# STC32G12K128.net
KiCad netlist of a schematic drawn in Altium Designer
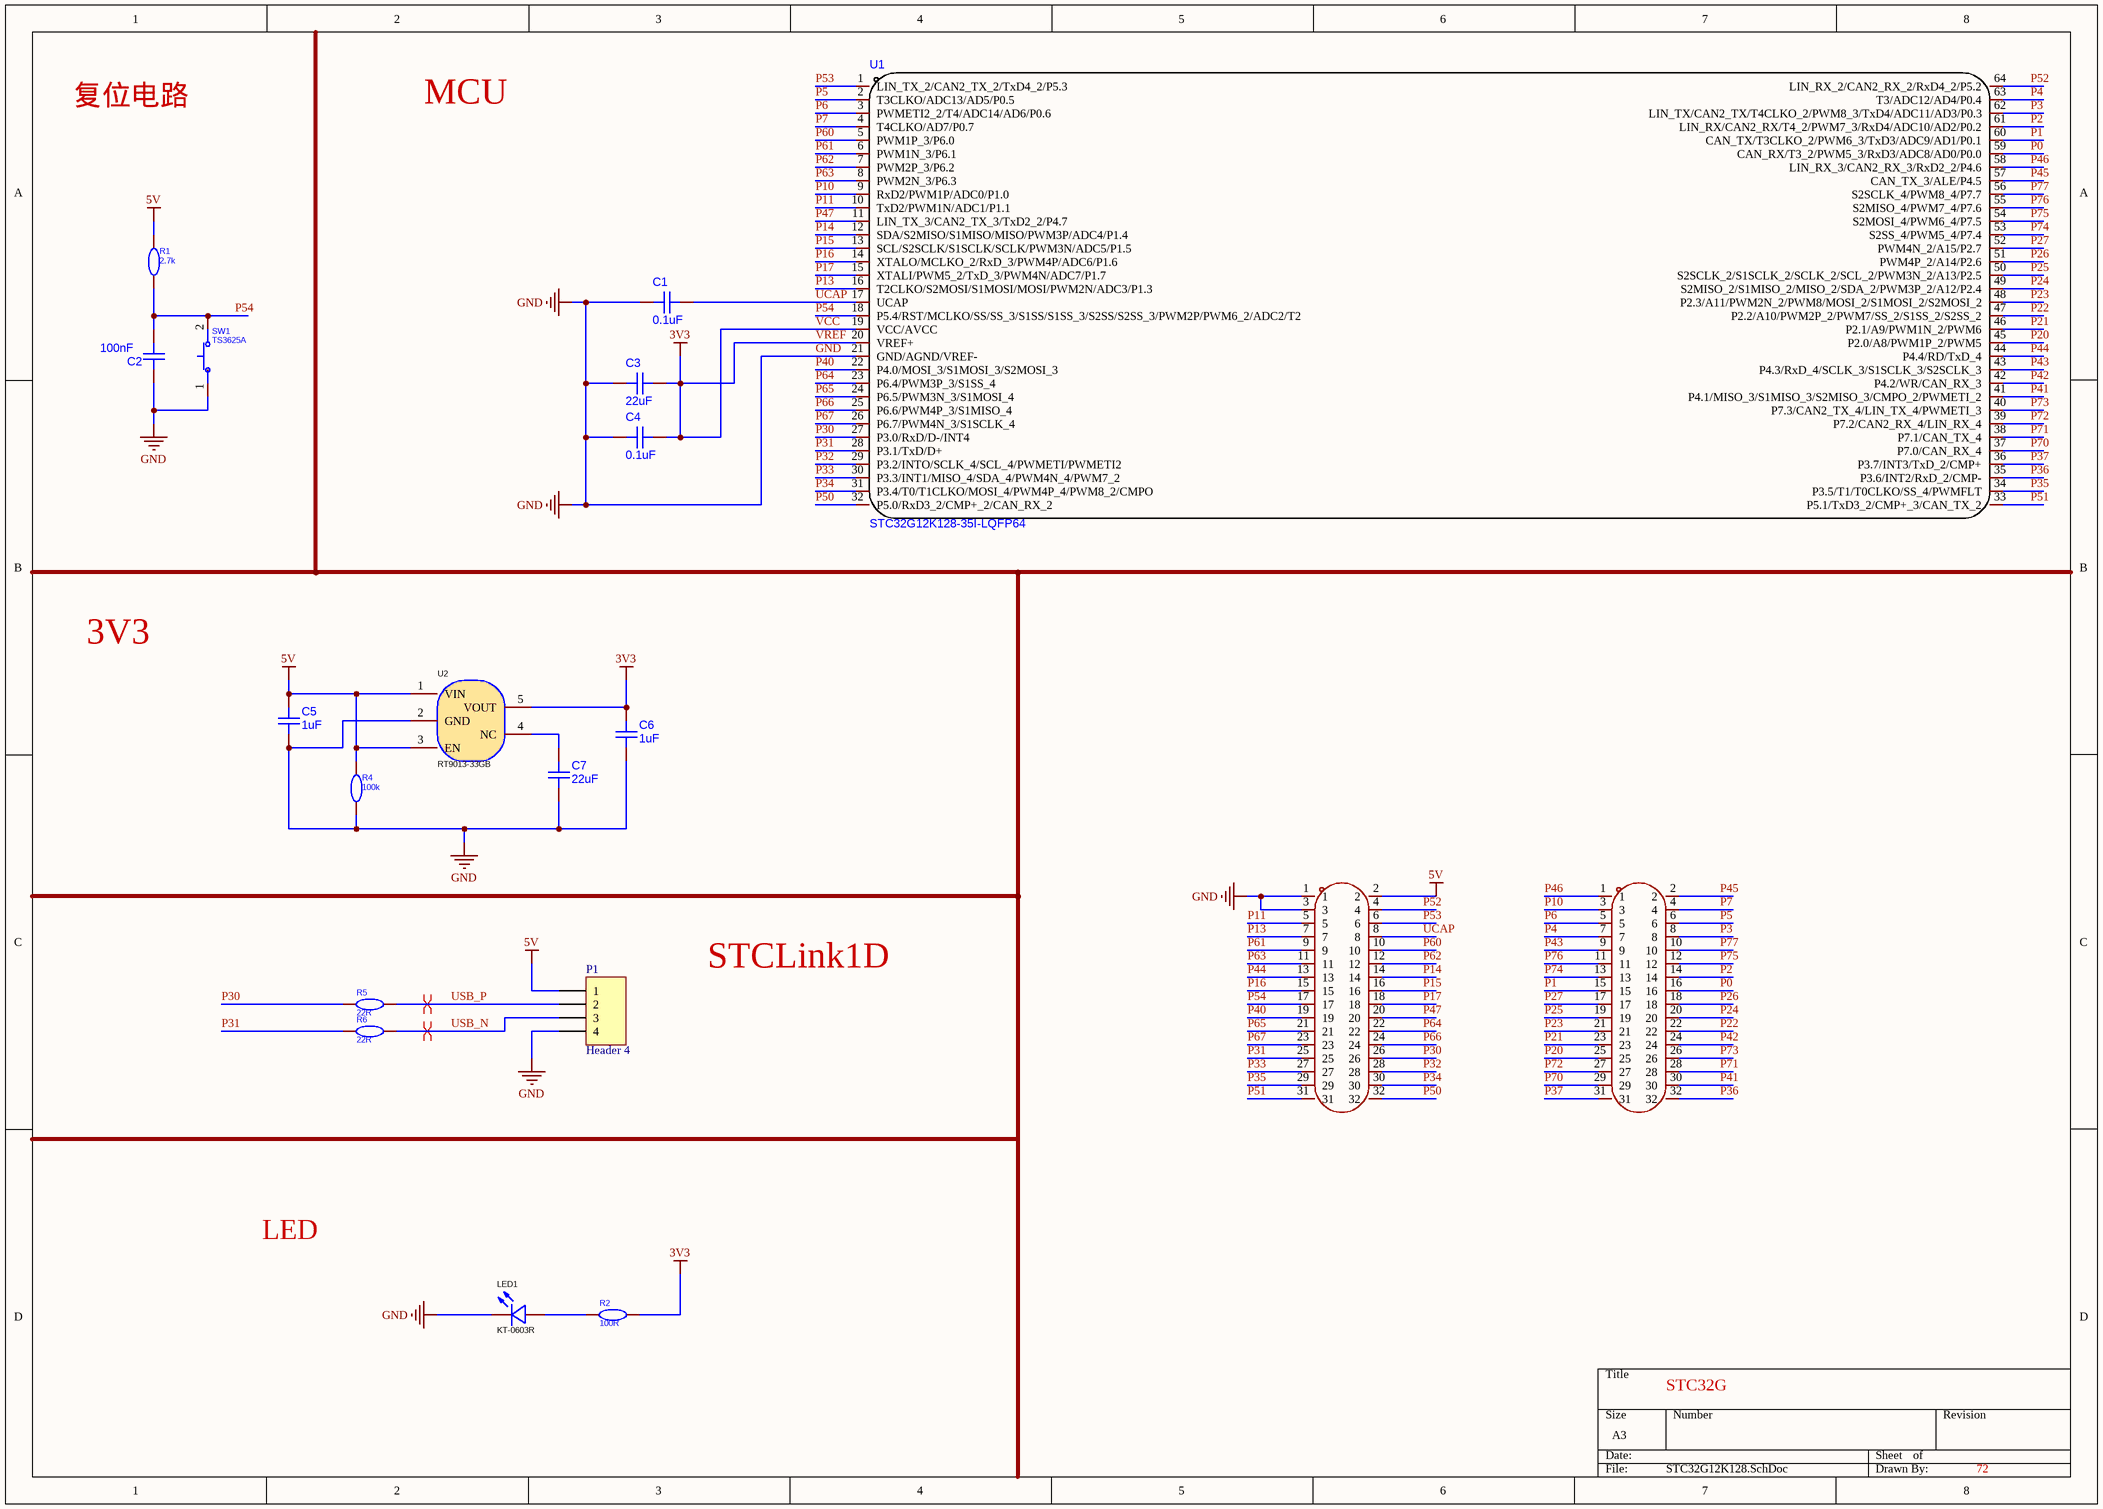
[diagram p0: STC32G12K128.SchDoc]

(export (version "E")
  (design (tool "Eeschema 10.0.6"))
  (components
    (comp (ref "C1")
      (value "0.1uF")
      (footprint "C0603:C0603")
      (fields
        (field (name "MANUFACTURER") "YAGEO(国巨)")
        (field (name "MANUFACTURER PART") "CC0603KRX7R9BB104")
        (field (name "TOLERANCE") "±10%")
      )
      (libsource (lib "CC0603KRX7R9BB1041_CC0603KRX7R9BB104") (part "CC0603KRX7R9BB104"))
    )
    (comp (ref "C2")
      (value "100nF")
      (footprint "C0603:C0603")
      (fields
        (field (name "MANUFACTURER") "YAGEO(国巨)")
        (field (name "MANUFACTURER PART") "CC0603KRX7R9BB104")
        (field (name "TOLERANCE") "±10%")
      )
      (libsource (lib "CC0603KRX7R9BB1041_CC0603KRX7R9BB104") (part "CC0603KRX7R9BB104"))
    )
    (comp (ref "C3")
      (value "22uF")
      (footprint "C0603:C0603")
      (fields
        (field (name "MANUFACTURER") "YAGEO(国巨)")
        (field (name "MANUFACTURER PART") "CC0603KRX7R9BB104")
        (field (name "TOLERANCE") "±10%")
      )
      (libsource (lib "CC0603KRX7R9BB1041_CC0603KRX7R9BB104") (part "CC0603KRX7R9BB104"))
    )
    (comp (ref "C4")
      (value "0.1uF")
      (footprint "C0603:C0603")
      (fields
        (field (name "MANUFACTURER") "YAGEO(国巨)")
        (field (name "MANUFACTURER PART") "CC0603KRX7R9BB104")
        (field (name "TOLERANCE") "±10%")
      )
      (libsource (lib "CC0603KRX7R9BB1041_CC0603KRX7R9BB104") (part "CC0603KRX7R9BB104"))
    )
    (comp (ref "C5")
      (value "1uF")
      (footprint "C0603:C0603")
      (fields
        (field (name "MANUFACTURER") "YAGEO(国巨)")
        (field (name "MANUFACTURER PART") "CC0603KRX7R9BB104")
        (field (name "TOLERANCE") "±10%")
      )
      (libsource (lib "CC0603KRX7R9BB1041_CC0603KRX7R9BB104") (part "CC0603KRX7R9BB104"))
    )
    (comp (ref "C6")
      (value "1uF")
      (footprint "C0603:C0603")
      (fields
        (field (name "MANUFACTURER") "YAGEO(国巨)")
        (field (name "MANUFACTURER PART") "CC0603KRX7R9BB104")
        (field (name "TOLERANCE") "±10%")
      )
      (libsource (lib "CC0603KRX7R9BB1041_CC0603KRX7R9BB104") (part "CC0603KRX7R9BB104"))
    )
    (comp (ref "C7")
      (value "22uF")
      (footprint "C0603:C0603")
      (fields
        (field (name "MANUFACTURER") "YAGEO(国巨)")
        (field (name "MANUFACTURER PART") "CC0603KRX7R9BB104")
        (field (name "TOLERANCE") "±10%")
      )
      (libsource (lib "CC0603KRX7R9BB1041_CC0603KRX7R9BB104") (part "CC0603KRX7R9BB104"))
    )
    (comp (ref "H1")
      (value "X6521WV-2x16H-C60D30")
      (footprint "HDR-TH_32P-2.54-V-M-R2-C16-S2.54:HDR-TH_32P-2.54-V-M-R2-C16-S2.54")
      (fields (field (name "MANUFACTURER") "XKB Connection(中国星坤)"))
      (libsource (lib "2×16H") (part "X6521WV-2x16H-C60D30"))
    )
    (comp (ref "H2")
      (value "X6521WV-2x16H-C60D30")
      (footprint "HDR-TH_32P-2.54-V-M-R2-C16-S2.54:HDR-TH_32P-2.54-V-M-R2-C16-S2.54")
      (fields (field (name "MANUFACTURER") "XKB Connection(中国星坤)"))
      (libsource (lib "2×16H") (part "X6521WV-2x16H-C60D30"))
    )
    (comp (ref "LED1")
      (value "KT-0603R")
      (footprint "LED0603-RD (1):LED0603-RD")
      (fields (field (name "MANUFACTURER") "KENTO"))
      (libsource (lib "LED-Red") (part "KT-0603R"))
    )
    (comp (ref "P1")
      (value "Header 4")
      (footprint "HDR1X4")
      (description "Header, 4-Pin")
      (fields (field (name "PUBLISHER") "Altium Limited"))
      (libsource (lib "Miscellaneous Connectors") (part "Header 4"))
    )
    (comp (ref "R1")
      (value "2.7k")
      (footprint "R0603:R0603")
      (fields
        (field (name "MANUFACTURER") "YAGEO(国巨)")
        (field (name "MANUFACTURER PART") "RC0603FR-074K7L")
        (field (name "TOLERANCE") "±1%")
      )
      (libsource (lib "4.7-0603") (part "RC0603FR-074K7L"))
    )
    (comp (ref "R2")
      (value "100R")
      (footprint "R0603:R0603")
      (fields
        (field (name "MANUFACTURER") "YAGEO(国巨)")
        (field (name "MANUFACTURER PART") "RC0603FR-074K7L")
        (field (name "TOLERANCE") "±1%")
      )
      (libsource (lib "4.7-0603") (part "RC0603FR-074K7L"))
    )
    (comp (ref "R4")
      (value "100k")
      (footprint "R0603:R0603")
      (fields
        (field (name "MANUFACTURER") "YAGEO(国巨)")
        (field (name "MANUFACTURER PART") "RC0603FR-074K7L")
        (field (name "TOLERANCE") "±1%")
      )
      (libsource (lib "4.7-0603") (part "RC0603FR-074K7L"))
    )
    (comp (ref "R5")
      (value "22R")
      (footprint "R0603:R0603")
      (fields
        (field (name "MANUFACTURER") "YAGEO(国巨)")
        (field (name "MANUFACTURER PART") "RC0603FR-074K7L")
        (field (name "TOLERANCE") "±1%")
      )
      (libsource (lib "4.7-0603") (part "RC0603FR-074K7L"))
    )
    (comp (ref "R6")
      (value "22R")
      (footprint "R0603:R0603")
      (fields
        (field (name "MANUFACTURER") "YAGEO(国巨)")
        (field (name "MANUFACTURER PART") "RC0603FR-074K7L")
        (field (name "TOLERANCE") "±1%")
      )
      (libsource (lib "4.7-0603") (part "RC0603FR-074K7L"))
    )
    (comp (ref "SW1")
      (value "TS3625A")
      (footprint "KEY-SMD_L6.0-W3.5-LS8.4:KEY-SMD_L6.0-W3.5-LS8.4")
      (fields (field (name "MANUFACTURER") "SHOU HAN(首韩)"))
      (libsource (lib "Button-SMD") (part "TS3625A"))
    )
    (comp (ref "U1")
      (value "STC32G12K128-35I-LQFP64")
      (footprint "LQFP-64_L10.0-W10.0-P0.50-LS12.0-BL:LQFP-64_L10.0-W10.0-P0.50-LS12.0-BL")
      (fields (field (name "MANUFACTURER") "STC(宏晶)"))
      (libsource (lib "STC32G12K128-35I-LQFP64") (part "STC32G12K128-35I-LQFP64"))
    )
    (comp (ref "U2")
      (value "RT9013-33GB")
      (footprint "SOT-23-5_L3.0-W1.7-P0.95-LS2.8-BL:SOT-23-5_L3.0-W1.7-P0.95-LS2.8-BL")
      (fields (field (name "MANUFACTURER") "RICHTEK(立锜)"))
      (libsource (lib "RT9013-33GB1_RT9013-33GB") (part "RT9013-33GB"))
    )
  )
  (nets
    (net (code "1") (name "/P0") (class "Default")
      (node (ref "H1") (pin "16") (pinfunction "16_16") (pintype "passive"))
      (node (ref "U1") (pin "59") (pinfunction "CAN_RX/T3_2/PWM5_3/RxD3/ADC8/AD0/P0.0_59") (pintype "passive"))
    )
    (net (code "2") (name "/P1") (class "Default")
      (node (ref "H1") (pin "15") (pinfunction "15_15") (pintype "passive"))
      (node (ref "U1") (pin "60") (pinfunction "CAN_TX/T3CLKO_2/PWM6_3/TxD3/ADC9/AD1/P0.1_60") (pintype "passive"))
    )
    (net (code "3") (name "/P2") (class "Default")
      (node (ref "H1") (pin "14") (pinfunction "14_14") (pintype "passive"))
      (node (ref "U1") (pin "61") (pinfunction "LIN_RX/CAN2_RX/T4_2/PWM7_3/RxD4/ADC10/AD2/P0.2_61") (pintype "passive"))
    )
    (net (code "4") (name "/P3") (class "Default")
      (node (ref "H1") (pin "8") (pinfunction "8_8") (pintype "passive"))
      (node (ref "U1") (pin "62") (pinfunction "LIN_TX/CAN2_TX/T4CLKO_2/PWM8_3/TxD4/ADC11/AD3/P0.3_62") (pintype "passive"))
    )
    (net (code "5") (name "/P4") (class "Default")
      (node (ref "H1") (pin "7") (pinfunction "7_7") (pintype "passive"))
      (node (ref "U1") (pin "63") (pinfunction "T3/ADC12/AD4/P0.4_63") (pintype "passive"))
    )
    (net (code "6") (name "/P5") (class "Default")
      (node (ref "H1") (pin "6") (pinfunction "6_6") (pintype "passive"))
      (node (ref "U1") (pin "2") (pinfunction "T3CLKO/ADC13/AD5/P0.5_2") (pintype "passive"))
    )
    (net (code "7") (name "/P6") (class "Default")
      (node (ref "H1") (pin "5") (pinfunction "5_5") (pintype "passive"))
      (node (ref "U1") (pin "3") (pinfunction "PWMETI2_2/T4/ADC14/AD6/P0.6_3") (pintype "passive"))
    )
    (net (code "8") (name "/P7") (class "Default")
      (node (ref "H1") (pin "4") (pinfunction "4_4") (pintype "passive"))
      (node (ref "U1") (pin "4") (pinfunction "T4CLKO/AD7/P0.7_4") (pintype "passive"))
    )
    (net (code "9") (name "/P10") (class "Default")
      (node (ref "H1") (pin "3") (pinfunction "3_3") (pintype "passive"))
      (node (ref "U1") (pin "9") (pinfunction "RxD2/PWM1P/ADC0/P1.0_9") (pintype "passive"))
    )
    (net (code "10") (name "/P11") (class "Default")
      (node (ref "H2") (pin "5") (pinfunction "5_5") (pintype "passive"))
      (node (ref "U1") (pin "10") (pinfunction "TxD2/PWM1N/ADC1/P1.1_10") (pintype "passive"))
    )
    (net (code "11") (name "/P13") (class "Default")
      (node (ref "H2") (pin "7") (pinfunction "7_7") (pintype "passive"))
      (node (ref "U1") (pin "16") (pinfunction "T2CLKO/S2MOSI/S1MOSI/MOSI/PWM2N/ADC3/P1.3_16") (pintype "passive"))
    )
    (net (code "12") (name "/P14") (class "Default")
      (node (ref "H2") (pin "14") (pinfunction "14_14") (pintype "passive"))
      (node (ref "U1") (pin "12") (pinfunction "SDA/S2MISO/S1MISO/MISO/PWM3P/ADC4/P1.4_12") (pintype "passive"))
    )
    (net (code "13") (name "/P15") (class "Default")
      (node (ref "H2") (pin "16") (pinfunction "16_16") (pintype "passive"))
      (node (ref "U1") (pin "13") (pinfunction "SCL/S2SCLK/S1SCLK/SCLK/PWM3N/ADC5/P1.5_13") (pintype "passive"))
    )
    (net (code "14") (name "/P16") (class "Default")
      (node (ref "H2") (pin "15") (pinfunction "15_15") (pintype "passive"))
      (node (ref "U1") (pin "14") (pinfunction "XTALO/MCLKO_2/RxD_3/PWM4P/ADC6/P1.6_14") (pintype "passive"))
    )
    (net (code "15") (name "/P17") (class "Default")
      (node (ref "H2") (pin "18") (pinfunction "18_18") (pintype "passive"))
      (node (ref "U1") (pin "15") (pinfunction "XTALI/PWM5_2/TxD_3/PWM4N/ADC7/P1.7_15") (pintype "passive"))
    )
    (net (code "16") (name "/P20") (class "Default")
      (node (ref "H1") (pin "25") (pinfunction "25_25") (pintype "passive"))
      (node (ref "U1") (pin "45") (pinfunction "P2.0/A8/PWM1P_2/PWM5_45") (pintype "passive"))
    )
    (net (code "17") (name "/P21") (class "Default")
      (node (ref "H1") (pin "23") (pinfunction "23_23") (pintype "passive"))
      (node (ref "U1") (pin "46") (pinfunction "P2.1/A9/PWM1N_2/PWM6_46") (pintype "passive"))
    )
    (net (code "18") (name "/P22") (class "Default")
      (node (ref "H1") (pin "22") (pinfunction "22_22") (pintype "passive"))
      (node (ref "U1") (pin "47") (pinfunction "P2.2/A10/PWM2P_2/PWM7/SS_2/S1SS_2/S2SS_2_47") (pintype "passive"))
    )
    (net (code "19") (name "/P23") (class "Default")
      (node (ref "H1") (pin "21") (pinfunction "21_21") (pintype "passive"))
      (node (ref "U1") (pin "48") (pinfunction "P2.3/A11/PWM2N_2/PWM8/MOSI_2/S1MOSI_2/S2MOSI_2_48") (pintype "passive"))
    )
    (net (code "20") (name "/P24") (class "Default")
      (node (ref "H1") (pin "20") (pinfunction "20_20") (pintype "passive"))
      (node (ref "U1") (pin "49") (pinfunction "S2MISO_2/S1MISO_2/MISO_2/SDA_2/PWM3P_2/A12/P2.4_49") (pintype "passive"))
    )
    (net (code "21") (name "/P25") (class "Default")
      (node (ref "H1") (pin "19") (pinfunction "19_19") (pintype "passive"))
      (node (ref "U1") (pin "50") (pinfunction "S2SCLK_2/S1SCLK_2/SCLK_2/SCL_2/PWM3N_2/A13/P2.5_50") (pintype "passive"))
    )
    (net (code "22") (name "/P26") (class "Default")
      (node (ref "H1") (pin "18") (pinfunction "18_18") (pintype "passive"))
      (node (ref "U1") (pin "51") (pinfunction "PWM4P_2/A14/P2.6_51") (pintype "passive"))
    )
    (net (code "23") (name "/P27") (class "Default")
      (node (ref "H1") (pin "17") (pinfunction "17_17") (pintype "passive"))
      (node (ref "U1") (pin "52") (pinfunction "PWM4N_2/A15/P2.7_52") (pintype "passive"))
    )
    (net (code "24") (name "/P30") (class "Default")
      (node (ref "H2") (pin "26") (pinfunction "26_26") (pintype "passive"))
      (node (ref "R5") (pin "2") (pinfunction "2_2") (pintype "passive"))
      (node (ref "U1") (pin "27") (pinfunction "P3.0/RxD/D-/INT4_27") (pintype "passive"))
    )
    (net (code "25") (name "/P31") (class "Default")
      (node (ref "H2") (pin "25") (pinfunction "25_25") (pintype "passive"))
      (node (ref "R6") (pin "2") (pinfunction "2_2") (pintype "passive"))
      (node (ref "U1") (pin "28") (pinfunction "P3.1/TxD/D+_28") (pintype "passive"))
    )
    (net (code "26") (name "/P32") (class "Default")
      (node (ref "H2") (pin "28") (pinfunction "28_28") (pintype "passive"))
      (node (ref "U1") (pin "29") (pinfunction "P3.2/INTO/SCLK_4/SCL_4/PWMETI/PWMETI2_29") (pintype "passive"))
    )
    (net (code "27") (name "/P33") (class "Default")
      (node (ref "H2") (pin "27") (pinfunction "27_27") (pintype "passive"))
      (node (ref "U1") (pin "30") (pinfunction "P3.3/INT1/MISO_4/SDA_4/PWM4N_4/PWM7_2_30") (pintype "passive"))
    )
    (net (code "28") (name "/P34") (class "Default")
      (node (ref "H2") (pin "30") (pinfunction "30_30") (pintype "passive"))
      (node (ref "U1") (pin "31") (pinfunction "P3.4/T0/T1CLKO/MOSI_4/PWM4P_4/PWM8_2/CMPO_31") (pintype "passive"))
    )
    (net (code "29") (name "/P35") (class "Default")
      (node (ref "H2") (pin "29") (pinfunction "29_29") (pintype "passive"))
      (node (ref "U1") (pin "34") (pinfunction "P3.5/T1/T0CLKO/SS_4/PWMFLT_34") (pintype "passive"))
    )
    (net (code "30") (name "/P36") (class "Default")
      (node (ref "H1") (pin "32") (pinfunction "32_32") (pintype "passive"))
      (node (ref "U1") (pin "35") (pinfunction "P3.6/INT2/RxD_2/CMP-_35") (pintype "passive"))
    )
    (net (code "31") (name "/P37") (class "Default")
      (node (ref "H1") (pin "31") (pinfunction "31_31") (pintype "passive"))
      (node (ref "U1") (pin "36") (pinfunction "P3.7/INT3/TxD_2/CMP+_36") (pintype "passive"))
    )
    (net (code "32") (name "/P40") (class "Default")
      (node (ref "H2") (pin "19") (pinfunction "19_19") (pintype "passive"))
      (node (ref "U1") (pin "22") (pinfunction "P4.0/MOSI_3/S1MOSI_3/S2MOSI_3_22") (pintype "passive"))
    )
    (net (code "33") (name "/P41") (class "Default")
      (node (ref "H1") (pin "30") (pinfunction "30_30") (pintype "passive"))
      (node (ref "U1") (pin "41") (pinfunction "P4.1/MISO_3/S1MISO_3/S2MISO_3/CMPO_2/PWMETI_2_41") (pintype "passive"))
    )
    (net (code "34") (name "/P42") (class "Default")
      (node (ref "H1") (pin "24") (pinfunction "24_24") (pintype "passive"))
      (node (ref "U1") (pin "42") (pinfunction "P4.2/WR/CAN_RX_3_42") (pintype "passive"))
    )
    (net (code "35") (name "/P43") (class "Default")
      (node (ref "H1") (pin "9") (pinfunction "9_9") (pintype "passive"))
      (node (ref "U1") (pin "43") (pinfunction "P4.3/RxD_4/SCLK_3/S1SCLK_3/S2SCLK_3_43") (pintype "passive"))
    )
    (net (code "36") (name "/P44") (class "Default")
      (node (ref "H2") (pin "13") (pinfunction "13_13") (pintype "passive"))
      (node (ref "U1") (pin "44") (pinfunction "P4.4/RD/TxD_4_44") (pintype "passive"))
    )
    (net (code "37") (name "/P45") (class "Default")
      (node (ref "H1") (pin "2") (pinfunction "2_2") (pintype "passive"))
      (node (ref "U1") (pin "57") (pinfunction "CAN_TX_3/ALE/P4.5_57") (pintype "passive"))
    )
    (net (code "38") (name "/P46") (class "Default")
      (node (ref "H1") (pin "1") (pinfunction "1_1") (pintype "passive"))
      (node (ref "U1") (pin "58") (pinfunction "LIN_RX_3/CAN2_RX_3/RxD2_2/P4.6_58") (pintype "passive"))
    )
    (net (code "39") (name "/P47") (class "Default")
      (node (ref "H2") (pin "20") (pinfunction "20_20") (pintype "passive"))
      (node (ref "U1") (pin "11") (pinfunction "LIN_TX_3/CAN2_TX_3/TxD2_2/P4.7_11") (pintype "passive"))
    )
    (net (code "40") (name "/P50") (class "Default")
      (node (ref "H2") (pin "32") (pinfunction "32_32") (pintype "passive"))
      (node (ref "U1") (pin "32") (pinfunction "P5.0/RxD3_2/CMP+_2/CAN_RX_2_32") (pintype "passive"))
    )
    (net (code "41") (name "/P51") (class "Default")
      (node (ref "H2") (pin "31") (pinfunction "31_31") (pintype "passive"))
      (node (ref "U1") (pin "33") (pinfunction "P5.1/TxD3_2/CMP+_3/CAN_TX_2_33") (pintype "passive"))
    )
    (net (code "42") (name "/P52") (class "Default")
      (node (ref "H2") (pin "4") (pinfunction "4_4") (pintype "passive"))
      (node (ref "U1") (pin "64") (pinfunction "LIN_RX_2/CAN2_RX_2/RxD4_2/P5.2_64") (pintype "passive"))
    )
    (net (code "43") (name "/P53") (class "Default")
      (node (ref "H2") (pin "6") (pinfunction "6_6") (pintype "passive"))
      (node (ref "U1") (pin "1") (pinfunction "LIN_TX_2/CAN2_TX_2/TxD4_2/P5.3_1") (pintype "passive"))
    )
    (net (code "44") (name "/P54") (class "Default")
      (node (ref "C2") (pin "2") (pinfunction "2_2") (pintype "passive"))
      (node (ref "H2") (pin "17") (pinfunction "17_17") (pintype "passive"))
      (node (ref "R1") (pin "1") (pinfunction "1_1") (pintype "passive"))
      (node (ref "SW1") (pin "2") (pinfunction "2_2") (pintype "passive"))
      (node (ref "U1") (pin "18") (pinfunction "P5.4/RST/MCLKO/SS/SS_3/S1SS/S1SS_3/S2SS/S2SS_3/PWM2P/PWM6_2/ADC2/T2_18") (pintype "passive"))
    )
    (net (code "45") (name "/P60") (class "Default")
      (node (ref "H2") (pin "10") (pinfunction "10_10") (pintype "passive"))
      (node (ref "U1") (pin "5") (pinfunction "PWM1P_3/P6.0_5") (pintype "passive"))
    )
    (net (code "46") (name "/P61") (class "Default")
      (node (ref "H2") (pin "9") (pinfunction "9_9") (pintype "passive"))
      (node (ref "U1") (pin "6") (pinfunction "PWM1N_3/P6.1_6") (pintype "passive"))
    )
    (net (code "47") (name "/P62") (class "Default")
      (node (ref "H2") (pin "12") (pinfunction "12_12") (pintype "passive"))
      (node (ref "U1") (pin "7") (pinfunction "PWM2P_3/P6.2_7") (pintype "passive"))
    )
    (net (code "48") (name "/P63") (class "Default")
      (node (ref "H2") (pin "11") (pinfunction "11_11") (pintype "passive"))
      (node (ref "U1") (pin "8") (pinfunction "PWM2N_3/P6.3_8") (pintype "passive"))
    )
    (net (code "49") (name "/P64") (class "Default")
      (node (ref "H2") (pin "22") (pinfunction "22_22") (pintype "passive"))
      (node (ref "U1") (pin "23") (pinfunction "P6.4/PWM3P_3/S1SS_4_23") (pintype "passive"))
    )
    (net (code "50") (name "/P65") (class "Default")
      (node (ref "H2") (pin "21") (pinfunction "21_21") (pintype "passive"))
      (node (ref "U1") (pin "24") (pinfunction "P6.5/PWM3N_3/S1MOSI_4_24") (pintype "passive"))
    )
    (net (code "51") (name "/P66") (class "Default")
      (node (ref "H2") (pin "24") (pinfunction "24_24") (pintype "passive"))
      (node (ref "U1") (pin "25") (pinfunction "P6.6/PWM4P_3/S1MISO_4_25") (pintype "passive"))
    )
    (net (code "52") (name "/P67") (class "Default")
      (node (ref "H2") (pin "23") (pinfunction "23_23") (pintype "passive"))
      (node (ref "U1") (pin "26") (pinfunction "P6.7/PWM4N_3/S1SCLK_4_26") (pintype "passive"))
    )
    (net (code "53") (name "/P70") (class "Default")
      (node (ref "H1") (pin "29") (pinfunction "29_29") (pintype "passive"))
      (node (ref "U1") (pin "37") (pinfunction "P7.0/CAN_RX_4_37") (pintype "passive"))
    )
    (net (code "54") (name "/P71") (class "Default")
      (node (ref "H1") (pin "28") (pinfunction "28_28") (pintype "passive"))
      (node (ref "U1") (pin "38") (pinfunction "P7.1/CAN_TX_4_38") (pintype "passive"))
    )
    (net (code "55") (name "/P72") (class "Default")
      (node (ref "H1") (pin "27") (pinfunction "27_27") (pintype "passive"))
      (node (ref "U1") (pin "39") (pinfunction "P7.2/CAN2_RX_4/LIN_RX_4_39") (pintype "passive"))
    )
    (net (code "56") (name "/P73") (class "Default")
      (node (ref "H1") (pin "26") (pinfunction "26_26") (pintype "passive"))
      (node (ref "U1") (pin "40") (pinfunction "P7.3/CAN2_TX_4/LIN_TX_4/PWMETI_3_40") (pintype "passive"))
    )
    (net (code "57") (name "/P74") (class "Default")
      (node (ref "H1") (pin "13") (pinfunction "13_13") (pintype "passive"))
      (node (ref "U1") (pin "53") (pinfunction "S2SS_4/PWM5_4/P7.4_53") (pintype "passive"))
    )
    (net (code "58") (name "/P75") (class "Default")
      (node (ref "H1") (pin "12") (pinfunction "12_12") (pintype "passive"))
      (node (ref "U1") (pin "54") (pinfunction "S2MOSI_4/PWM6_4/P7.5_54") (pintype "passive"))
    )
    (net (code "59") (name "/P76") (class "Default")
      (node (ref "H1") (pin "11") (pinfunction "11_11") (pintype "passive"))
      (node (ref "U1") (pin "55") (pinfunction "S2MISO_4/PWM7_4/P7.6_55") (pintype "passive"))
    )
    (net (code "60") (name "/P77") (class "Default")
      (node (ref "H1") (pin "10") (pinfunction "10_10") (pintype "passive"))
      (node (ref "U1") (pin "56") (pinfunction "S2SCLK_4/PWM8_4/P7.7_56") (pintype "passive"))
    )
    (net (code "61") (name "/UCAP") (class "Default")
      (node (ref "C1") (pin "1") (pinfunction "1_1") (pintype "passive"))
      (node (ref "H2") (pin "8") (pinfunction "8_8") (pintype "passive"))
      (node (ref "U1") (pin "17") (pinfunction "UCAP_17") (pintype "passive"))
    )
    (net (code "62") (name "/USB_N") (class "Default")
      (node (ref "P1") (pin "3") (pinfunction "3_3") (pintype "passive"))
      (node (ref "R6") (pin "1") (pinfunction "1_1") (pintype "passive"))
    )
    (net (code "63") (name "/USB_P") (class "Default")
      (node (ref "P1") (pin "2") (pinfunction "2_2") (pintype "passive"))
      (node (ref "R5") (pin "1") (pinfunction "1_1") (pintype "passive"))
    )
    (net (code "64") (name "3V3") (class "Default")
      (node (ref "C3") (pin "1") (pinfunction "1_1") (pintype "passive"))
      (node (ref "C4") (pin "1") (pinfunction "1_1") (pintype "passive"))
      (node (ref "C6") (pin "1") (pinfunction "1_1") (pintype "passive"))
      (node (ref "R2") (pin "1") (pinfunction "1_1") (pintype "passive"))
      (node (ref "U1") (pin "19") (pinfunction "VCC/AVCC_19") (pintype "passive"))
      (node (ref "U1") (pin "20") (pinfunction "VREF+_20") (pintype "passive"))
      (node (ref "U2") (pin "5") (pinfunction "VOUT_5") (pintype "passive"))
    )
    (net (code "65") (name "5V") (class "Default")
      (node (ref "C5") (pin "1") (pinfunction "1_1") (pintype "passive"))
      (node (ref "H2") (pin "2") (pinfunction "2_2") (pintype "passive"))
      (node (ref "P1") (pin "1") (pinfunction "1_1") (pintype "passive"))
      (node (ref "R1") (pin "2") (pinfunction "2_2") (pintype "passive"))
      (node (ref "R4") (pin "2") (pinfunction "2_2") (pintype "passive"))
      (node (ref "U2") (pin "1") (pinfunction "VIN_1") (pintype "passive"))
      (node (ref "U2") (pin "3") (pinfunction "EN_3") (pintype "passive"))
    )
    (net (code "66") (name "GND") (class "Default")
      (node (ref "C1") (pin "2") (pinfunction "2_2") (pintype "passive"))
      (node (ref "C2") (pin "1") (pinfunction "1_1") (pintype "passive"))
      (node (ref "C3") (pin "2") (pinfunction "2_2") (pintype "passive"))
      (node (ref "C4") (pin "2") (pinfunction "2_2") (pintype "passive"))
      (node (ref "C5") (pin "2") (pinfunction "2_2") (pintype "passive"))
      (node (ref "C6") (pin "2") (pinfunction "2_2") (pintype "passive"))
      (node (ref "C7") (pin "2") (pinfunction "2_2") (pintype "passive"))
      (node (ref "H2") (pin "1") (pinfunction "1_1") (pintype "passive"))
      (node (ref "H2") (pin "3") (pinfunction "3_3") (pintype "passive"))
      (node (ref "LED1") (pin "1") (pinfunction "K_1") (pintype "passive"))
      (node (ref "P1") (pin "4") (pinfunction "4_4") (pintype "passive"))
      (node (ref "R4") (pin "1") (pinfunction "1_1") (pintype "passive"))
      (node (ref "SW1") (pin "1") (pinfunction "1_1") (pintype "passive"))
      (node (ref "U1") (pin "21") (pinfunction "GND/AGND/VREF-_21") (pintype "passive"))
      (node (ref "U2") (pin "2") (pinfunction "GND_2") (pintype "passive"))
    )
    (net (code "67") (name "Net-(LED1-A)") (class "Default")
      (node (ref "LED1") (pin "2") (pinfunction "A_2") (pintype "passive"))
      (node (ref "R2") (pin "2") (pinfunction "2_2") (pintype "passive"))
    )
    (net (code "68") (name "Net-(U2-NC)") (class "Default")
      (node (ref "C7") (pin "1") (pinfunction "1_1") (pintype "passive"))
      (node (ref "U2") (pin "4") (pinfunction "NC_4") (pintype "passive"))
    )
  )
)
